# Audio_Codec.net
KiCad netlist of a schematic drawn in Altium Designer
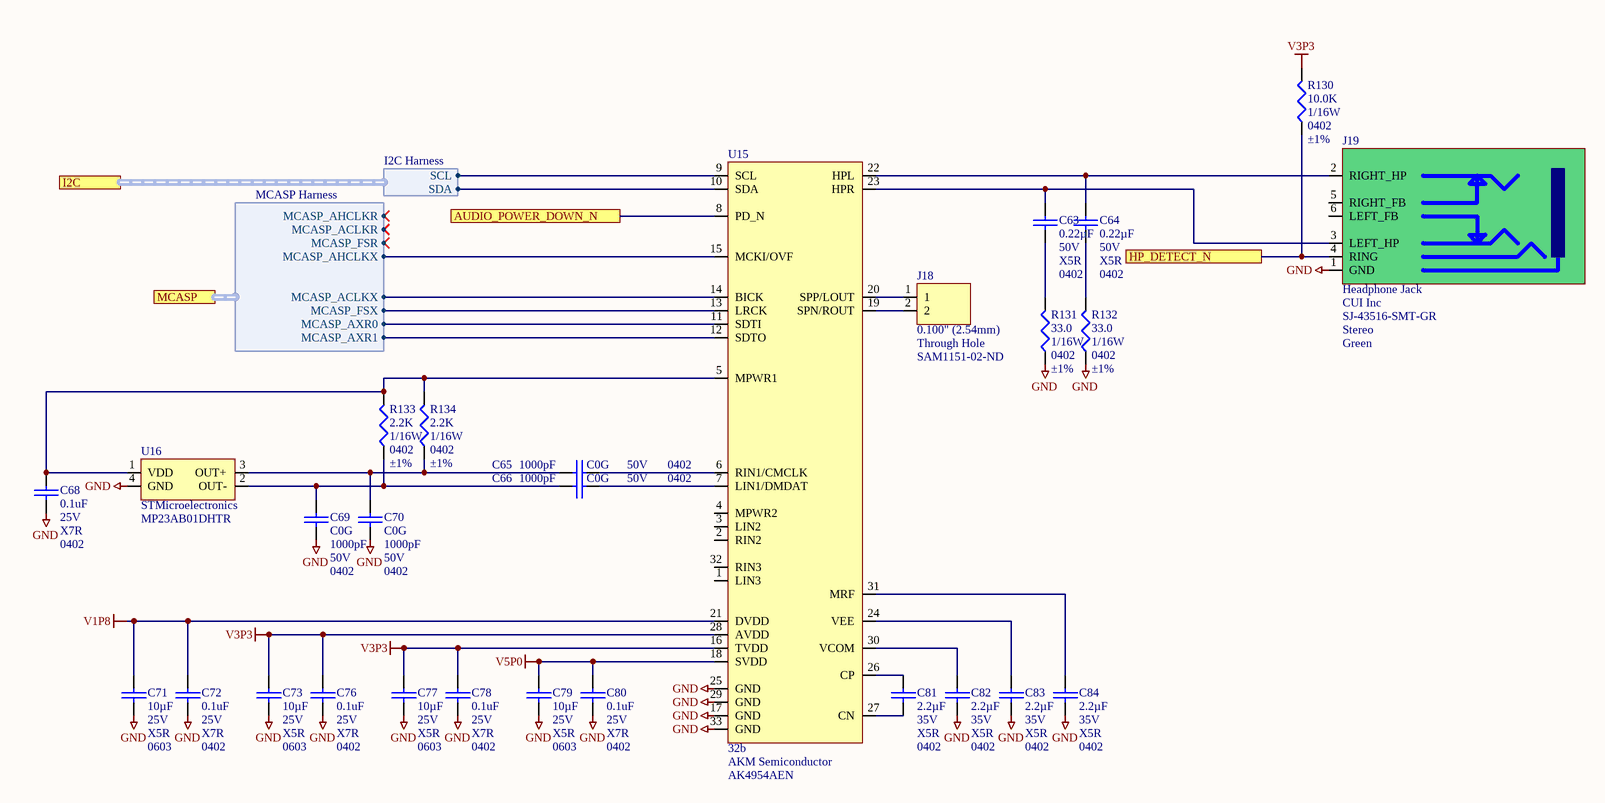
[diagram p0: Audio Codec.SchDoc]

(export (version "E")
  (design (tool "Eeschema 10.0.6"))
  (components
    (comp (ref "C63")
      (value "C_0402_0.22UF_50V")
      (footprint "C_ERA-0402")
      (description "CAP CER 0.22UF 50V X5R 0402")
      (fields
        (field (name "MANUFACTURER") "Taiyo Yuden")
        (field (name "MANUFACTURER PART NUMBER") "UMK105BJ224KV-F")
        (field (name "CAPACITANCE") "0.22µF")
        (field (name "VOLTAGE - RATED") "50V")
        (field (name "TEMPERATURE COEFFICIENT") "X5R")
        (field (name "PACKAGE / CASE") "0402")
      )
      (libsource (lib "Main Library") (part "C_0402_0.22UF_50V"))
    )
    (comp (ref "C64")
      (value "C_0402_0.22UF_50V")
      (footprint "C_ERA-0402")
      (description "CAP CER 0.22UF 50V X5R 0402")
      (fields
        (field (name "MANUFACTURER") "Taiyo Yuden")
        (field (name "MANUFACTURER PART NUMBER") "UMK105BJ224KV-F")
        (field (name "CAPACITANCE") "0.22µF")
        (field (name "VOLTAGE - RATED") "50V")
        (field (name "TEMPERATURE COEFFICIENT") "X5R")
        (field (name "PACKAGE / CASE") "0402")
      )
      (libsource (lib "Main Library") (part "C_0402_0.22UF_50V"))
    )
    (comp (ref "C65")
      (value "1000pF")
      (footprint "C_ERA-0402")
      (description "CAP CER 1000PF 50V C0G 0402")
      (fields
        (field (name "MANUFACTURER") "Murata Electronics North America")
        (field (name "MANUFACTURER PART NUMBER") "GRM1555C1H102JA01D")
        (field (name "TEMPERATURE COEFFICIENT") "C0G")
        (field (name "CAPACITANCE") "1000pF")
        (field (name "VOLTAGE - RATED") "50V")
        (field (name "PACKAGE / CASE") "0402")
      )
      (libsource (lib "Main Library") (part "C_0402_1000PF_50V"))
    )
    (comp (ref "C66")
      (value "1000pF")
      (footprint "C_ERA-0402")
      (description "CAP CER 1000PF 50V C0G 0402")
      (fields
        (field (name "MANUFACTURER") "Murata Electronics North America")
        (field (name "MANUFACTURER PART NUMBER") "GRM1555C1H102JA01D")
        (field (name "TEMPERATURE COEFFICIENT") "C0G")
        (field (name "CAPACITANCE") "1000pF")
        (field (name "VOLTAGE - RATED") "50V")
        (field (name "PACKAGE / CASE") "0402")
      )
      (libsource (lib "Main Library") (part "C_0402_1000PF_50V"))
    )
    (comp (ref "C68")
      (value "C_0402_0.1UF_25V")
      (footprint "C_0402")
      (description "CAP CER 0.1UF 25V X6S 0402")
      (fields
        (field (name "TOLERANCE") "10%")
        (field (name "CAPACITANCE") "0.1uF")
        (field (name "VOLTAGE - RATED") "25V")
        (field (name "TEMPERATURE COEFFICIENT") "X7R")
        (field (name "PACKAGE / CASE") "0402")
      )
      (libsource (lib "Cospan Design") (part "C_0402_0.1UF_25V"))
    )
    (comp (ref "C69")
      (value "1000pF")
      (footprint "C_ERA-0402")
      (description "CAP CER 1000PF 50V C0G 0402")
      (fields
        (field (name "MANUFACTURER") "Murata Electronics North America")
        (field (name "MANUFACTURER PART NUMBER") "GRM1555C1H102JA01D")
        (field (name "TEMPERATURE COEFFICIENT") "C0G")
        (field (name "CAPACITANCE") "1000pF")
        (field (name "VOLTAGE - RATED") "50V")
        (field (name "PACKAGE / CASE") "0402")
      )
      (libsource (lib "Main Library") (part "C_0402_1000PF_50V"))
    )
    (comp (ref "C70")
      (value "1000pF")
      (footprint "C_ERA-0402")
      (description "CAP CER 1000PF 50V C0G 0402")
      (fields
        (field (name "MANUFACTURER") "Murata Electronics North America")
        (field (name "MANUFACTURER PART NUMBER") "GRM1555C1H102JA01D")
        (field (name "TEMPERATURE COEFFICIENT") "C0G")
        (field (name "CAPACITANCE") "1000pF")
        (field (name "VOLTAGE - RATED") "50V")
        (field (name "PACKAGE / CASE") "0402")
      )
      (libsource (lib "Main Library") (part "C_0402_1000PF_50V"))
    )
    (comp (ref "C71")
      (value "C_0603_10µF")
      (footprint "C_ERA-0603")
      (description "CAP CER 10UF 16V X5R 0603")
      (fields
        (field (name "MANUFACTURER") "Murata Electronics North America")
        (field (name "MANUFACTURER PART NUMBER") "GRM188R61C106MA73D")
        (field (name "CAPACITANCE") "10µF")
        (field (name "VOLTAGE - RATED") "25V")
        (field (name "TEMPERATURE COEFFICIENT") "X5R")
        (field (name "PACKAGE / CASE") "0603")
      )
      (libsource (lib "Cospan Design") (part "C_0603_10µF"))
    )
    (comp (ref "C72")
      (value "C_0402_0.1UF_25V")
      (footprint "C_0402")
      (description "CAP CER 0.1UF 25V X6S 0402")
      (fields
        (field (name "TOLERANCE") "10%")
        (field (name "CAPACITANCE") "0.1uF")
        (field (name "VOLTAGE - RATED") "25V")
        (field (name "TEMPERATURE COEFFICIENT") "X7R")
        (field (name "PACKAGE / CASE") "0402")
      )
      (libsource (lib "Cospan Design") (part "C_0402_0.1UF_25V"))
    )
    (comp (ref "C73")
      (value "C_0603_10µF")
      (footprint "C_ERA-0603")
      (description "CAP CER 10UF 16V X5R 0603")
      (fields
        (field (name "MANUFACTURER") "Murata Electronics North America")
        (field (name "MANUFACTURER PART NUMBER") "GRM188R61C106MA73D")
        (field (name "CAPACITANCE") "10µF")
        (field (name "VOLTAGE - RATED") "25V")
        (field (name "TEMPERATURE COEFFICIENT") "X5R")
        (field (name "PACKAGE / CASE") "0603")
      )
      (libsource (lib "Cospan Design") (part "C_0603_10µF"))
    )
    (comp (ref "C76")
      (value "C_0402_0.1UF_25V")
      (footprint "C_0402")
      (description "CAP CER 0.1UF 25V X6S 0402")
      (fields
        (field (name "TOLERANCE") "10%")
        (field (name "CAPACITANCE") "0.1uF")
        (field (name "VOLTAGE - RATED") "25V")
        (field (name "TEMPERATURE COEFFICIENT") "X7R")
        (field (name "PACKAGE / CASE") "0402")
      )
      (libsource (lib "Cospan Design") (part "C_0402_0.1UF_25V"))
    )
    (comp (ref "C77")
      (value "C_0603_10µF")
      (footprint "C_ERA-0603")
      (description "CAP CER 10UF 16V X5R 0603")
      (fields
        (field (name "MANUFACTURER") "Murata Electronics North America")
        (field (name "MANUFACTURER PART NUMBER") "GRM188R61C106MA73D")
        (field (name "CAPACITANCE") "10µF")
        (field (name "VOLTAGE - RATED") "25V")
        (field (name "TEMPERATURE COEFFICIENT") "X5R")
        (field (name "PACKAGE / CASE") "0603")
      )
      (libsource (lib "Cospan Design") (part "C_0603_10µF"))
    )
    (comp (ref "C78")
      (value "C_0402_0.1UF_25V")
      (footprint "C_0402")
      (description "CAP CER 0.1UF 25V X6S 0402")
      (fields
        (field (name "TOLERANCE") "10%")
        (field (name "CAPACITANCE") "0.1uF")
        (field (name "VOLTAGE - RATED") "25V")
        (field (name "TEMPERATURE COEFFICIENT") "X7R")
        (field (name "PACKAGE / CASE") "0402")
      )
      (libsource (lib "Cospan Design") (part "C_0402_0.1UF_25V"))
    )
    (comp (ref "C79")
      (value "C_0603_10µF")
      (footprint "C_ERA-0603")
      (description "CAP CER 10UF 16V X5R 0603")
      (fields
        (field (name "MANUFACTURER") "Murata Electronics North America")
        (field (name "MANUFACTURER PART NUMBER") "GRM188R61C106MA73D")
        (field (name "CAPACITANCE") "10µF")
        (field (name "VOLTAGE - RATED") "25V")
        (field (name "TEMPERATURE COEFFICIENT") "X5R")
        (field (name "PACKAGE / CASE") "0603")
      )
      (libsource (lib "Cospan Design") (part "C_0603_10µF"))
    )
    (comp (ref "C80")
      (value "C_0402_0.1UF_25V")
      (footprint "C_0402")
      (description "CAP CER 0.1UF 25V X6S 0402")
      (fields
        (field (name "TOLERANCE") "10%")
        (field (name "CAPACITANCE") "0.1uF")
        (field (name "VOLTAGE - RATED") "25V")
        (field (name "TEMPERATURE COEFFICIENT") "X7R")
        (field (name "PACKAGE / CASE") "0402")
      )
      (libsource (lib "Cospan Design") (part "C_0402_0.1UF_25V"))
    )
    (comp (ref "C81")
      (value "C_0402_2.2uF_35V")
      (footprint "C_ERA-0402")
      (description "CAP CER 2.2UF 35V 20% X5R 0402")
      (fields
        (field (name "MANUFACTURER") "TDK Corporation")
        (field (name "MANUFACTURER PART NUMBER") "C1005X5R1V225K050BC")
        (field (name "CAPACITANCE") "2.2µF")
        (field (name "VOLTAGE - RATED") "35V")
        (field (name "TEMPERATURE COEFFICIENT") "X5R")
        (field (name "PACKAGE / CASE") "0402")
      )
      (libsource (lib "Main Library") (part "C_0402_2.2uF_35V"))
    )
    (comp (ref "C82")
      (value "C_0402_2.2uF_35V")
      (footprint "C_ERA-0402")
      (description "CAP CER 2.2UF 35V 20% X5R 0402")
      (fields
        (field (name "MANUFACTURER") "TDK Corporation")
        (field (name "MANUFACTURER PART NUMBER") "C1005X5R1V225K050BC")
        (field (name "CAPACITANCE") "2.2µF")
        (field (name "VOLTAGE - RATED") "35V")
        (field (name "TEMPERATURE COEFFICIENT") "X5R")
        (field (name "PACKAGE / CASE") "0402")
      )
      (libsource (lib "Main Library") (part "C_0402_2.2uF_35V"))
    )
    (comp (ref "C83")
      (value "C_0402_2.2uF_35V")
      (footprint "C_ERA-0402")
      (description "CAP CER 2.2UF 35V 20% X5R 0402")
      (fields
        (field (name "MANUFACTURER") "TDK Corporation")
        (field (name "MANUFACTURER PART NUMBER") "C1005X5R1V225K050BC")
        (field (name "CAPACITANCE") "2.2µF")
        (field (name "VOLTAGE - RATED") "35V")
        (field (name "TEMPERATURE COEFFICIENT") "X5R")
        (field (name "PACKAGE / CASE") "0402")
      )
      (libsource (lib "Main Library") (part "C_0402_2.2uF_35V"))
    )
    (comp (ref "C84")
      (value "C_0402_2.2uF_35V")
      (footprint "C_ERA-0402")
      (description "CAP CER 2.2UF 35V 20% X5R 0402")
      (fields
        (field (name "MANUFACTURER") "TDK Corporation")
        (field (name "MANUFACTURER PART NUMBER") "C1005X5R1V225K050BC")
        (field (name "CAPACITANCE") "2.2µF")
        (field (name "VOLTAGE - RATED") "35V")
        (field (name "TEMPERATURE COEFFICIENT") "X5R")
        (field (name "PACKAGE / CASE") "0402")
      )
      (libsource (lib "Main Library") (part "C_0402_2.2uF_35V"))
    )
    (comp (ref "J18")
      (value "J_HDR1X2_THRHOLE_VERT_FEMALE")
      (footprint "1X2_HOLES_VERTICAL_FEMALE_HEADRER")
      (description "CONN RCPT .100\" 2POS SNGL HORZ")
      (fields
        (field (name "MANUFACTURER") "Samtec Inc")
        (field (name "MANUFACTURER PART NUMBER") "SSM-102-S-SH")
        (field (name "PITCH") "0.100\" (2.54mm)")
        (field (name "MOUNTING TYPE") "Through Hole")
        (field (name "SUPPLIER PART NUMBER 1") "SAM1151-02-ND")
      )
      (libsource (lib "Main Library") (part "J_HDR1X2_THRHOLE_VERT_FEMALE"))
    )
    (comp (ref "J19")
      (value "Headphone Jack")
      (footprint "HEADPHONE_JACK")
      (description "CONN AUDIO JACK 3.5MM 4COND SMD")
      (fields
        (field (name "MANUFACTURER") "CUI Inc")
        (field (name "MANUFACTURER PART NUMBER") "SJ-43516-SMT-GR")
        (field (name "SIGNAL LINES") "Stereo")
        (field (name "COLOR") "Green")
      )
      (libsource (lib "Main Library") (part "J_HEADPHONE_JACK"))
    )
    (comp (ref "R130")
      (value "R_0402_10.0K")
      (footprint "R_0402")
      (description "RES 10.0K OHM 1/16W 1% 0402 SMD")
      (fields
        (field (name "MANUFACTURER") "Stackpole Electronics Inc")
        (field (name "MANUFACTURER PART NUMBER") "RMCF0402FT10K0")
        (field (name "RESISTANCE IN OHMS") "10.0K")
        (field (name "POWER (WATTS)") "1/16W")
        (field (name "CASE") "0402")
        (field (name "TOLERANCE") "±1%")
      )
      (libsource (lib "Main Library") (part "R_0402_10.0K"))
    )
    (comp (ref "R131")
      (value "R_0402_33")
      (footprint "R_0402")
      (description "RES 33.0 OHM 1/16W 1% 0402 SMD")
      (fields
        (field (name "MANUFACTURER") "Yageo")
        (field (name "MANUFACTURER PART NUMBER") "RC0402FR-0733RL")
        (field (name "RESISTANCE IN OHMS") "33.0")
        (field (name "POWER (WATTS)") "1/16W")
        (field (name "CASE") "0402")
        (field (name "TOLERANCE") "±1%")
      )
      (libsource (lib "Main Library") (part "R_0402_33"))
    )
    (comp (ref "R132")
      (value "R_0402_33")
      (footprint "R_0402")
      (description "RES 33.0 OHM 1/16W 1% 0402 SMD")
      (fields
        (field (name "MANUFACTURER") "Yageo")
        (field (name "MANUFACTURER PART NUMBER") "RC0402FR-0733RL")
        (field (name "RESISTANCE IN OHMS") "33.0")
        (field (name "POWER (WATTS)") "1/16W")
        (field (name "CASE") "0402")
        (field (name "TOLERANCE") "±1%")
      )
      (libsource (lib "Main Library") (part "R_0402_33"))
    )
    (comp (ref "R133")
      (value "R_0402_2.2K")
      (footprint "R_0402")
      (description "RES SMD 2.2K OHM 1% 1/10W 0402")
      (fields
        (field (name "MANUFACTURER") "Panasonic Electronic Components")
        (field (name "MANUFACTURER PART NUMBER") "ERJ-2RKF2201X")
        (field (name "RESISTANCE IN OHMS") "2.2K")
        (field (name "POWER (WATTS)") "1/16W")
        (field (name "CASE") "0402")
        (field (name "TOLERANCE") "±1%")
      )
      (libsource (lib "Cospan Design") (part "R_0402_2.2K"))
    )
    (comp (ref "R134")
      (value "R_0402_2.2K")
      (footprint "R_0402")
      (description "RES SMD 2.2K OHM 1% 1/10W 0402")
      (fields
        (field (name "MANUFACTURER") "Panasonic Electronic Components")
        (field (name "MANUFACTURER PART NUMBER") "ERJ-2RKF2201X")
        (field (name "RESISTANCE IN OHMS") "2.2K")
        (field (name "POWER (WATTS)") "1/16W")
        (field (name "CASE") "0402")
        (field (name "TOLERANCE") "±1%")
      )
      (libsource (lib "Cospan Design") (part "R_0402_2.2K"))
    )
    (comp (ref "U15")
      (value "U_AK4954AEN")
      (footprint "QFN40P400X400X80_HS-33N")
      (description "IC STEREO CODEC 32BIT 32QFN")
      (fields
        (field (name "RESOLUTION") "32b")
        (field (name "MANUFACTURER 1") "AKM Semiconductor")
        (field (name "MANUFACTURER PART NUMBER 1") "AK4954AEN")
      )
      (libsource (lib "Cospan Design") (part "U_AK4954AEN"))
    )
    (comp (ref "U16")
      (value "U_MP23AB01DHTR")
      (footprint "RHLGA")
      (description "MIC MEMS ANALOG OMNI -38DB")
      (fields
        (field (name "MANUFACTURER 1") "STMicroelectronics")
        (field (name "MANUFACTURER PART NUMBER 1") "MP23AB01DHTR")
      )
      (libsource (lib "Cospan Design") (part "U_MP23AB01DHTR"))
    )
  )
  (nets
    (net (code "4") (name "/AUDIO_POWER_DOWN_N") (class "Default")
      (node (ref "U15") (pin "8") (pinfunction "PD_N_8") (pintype "passive"))
    )
    (net (code "5") (name "/HP_DETECT_N") (class "Default")
      (node (ref "J19") (pin "4") (pinfunction "RING_4") (pintype "passive"))
      (node (ref "R130") (pin "2") (pinfunction "2_2") (pintype "passive"))
    )
    (net (code "6") (name "/MCASP_ACLKX") (class "Default")
      (node (ref "U15") (pin "14") (pinfunction "BICK_14") (pintype "passive"))
    )
    (net (code "7") (name "/MCASP_AHCLKX") (class "Default")
      (node (ref "U15") (pin "15") (pinfunction "MCKI/OVF_15") (pintype "passive"))
    )
    (net (code "8") (name "/MCASP_AXR0") (class "Default")
      (node (ref "U15") (pin "11") (pinfunction "SDTI_11") (pintype "passive"))
    )
    (net (code "9") (name "/MCASP_AXR1") (class "Default")
      (node (ref "U15") (pin "12") (pinfunction "SDTO_12") (pintype "passive"))
    )
    (net (code "10") (name "/MCASP_FSX") (class "Default")
      (node (ref "U15") (pin "13") (pinfunction "LRCK_13") (pintype "passive"))
    )
    (net (code "11") (name "/SCL") (class "Default")
      (node (ref "U15") (pin "9") (pinfunction "SCL_9") (pintype "passive"))
    )
    (net (code "12") (name "/SDA") (class "Default")
      (node (ref "U15") (pin "10") (pinfunction "SDA_10") (pintype "passive"))
    )
    (net (code "15") (name "GND") (class "Default")
      (node (ref "C68") (pin "1") (pinfunction "1_1") (pintype "passive"))
      (node (ref "C69") (pin "2") (pinfunction "2_2") (pintype "passive"))
      (node (ref "C70") (pin "2") (pinfunction "2_2") (pintype "passive"))
      (node (ref "C71") (pin "1") (pinfunction "1_1") (pintype "passive"))
      (node (ref "C72") (pin "1") (pinfunction "1_1") (pintype "passive"))
      (node (ref "C73") (pin "1") (pinfunction "1_1") (pintype "passive"))
      (node (ref "C76") (pin "1") (pinfunction "1_1") (pintype "passive"))
      (node (ref "C77") (pin "1") (pinfunction "1_1") (pintype "passive"))
      (node (ref "C78") (pin "1") (pinfunction "1_1") (pintype "passive"))
      (node (ref "C79") (pin "1") (pinfunction "1_1") (pintype "passive"))
      (node (ref "C80") (pin "1") (pinfunction "1_1") (pintype "passive"))
      (node (ref "C82") (pin "1") (pinfunction "1_1") (pintype "passive"))
      (node (ref "C83") (pin "1") (pinfunction "1_1") (pintype "passive"))
      (node (ref "C84") (pin "1") (pinfunction "1_1") (pintype "passive"))
      (node (ref "J19") (pin "1") (pinfunction "GND_1") (pintype "passive"))
      (node (ref "R131") (pin "2") (pinfunction "2_2") (pintype "passive"))
      (node (ref "R132") (pin "2") (pinfunction "2_2") (pintype "passive"))
      (node (ref "U15") (pin "17") (pinfunction "GND_17") (pintype "passive"))
      (node (ref "U15") (pin "25") (pinfunction "GND_25") (pintype "passive"))
      (node (ref "U15") (pin "29") (pinfunction "GND_29") (pintype "passive"))
      (node (ref "U15") (pin "33") (pinfunction "GND_33") (pintype "passive"))
      (node (ref "U16") (pin "4") (pinfunction "GND_4") (pintype "passive"))
    )
    (net (code "16") (name "Net-(C63-Pad1)") (class "Default")
      (node (ref "C63") (pin "1") (pinfunction "1_1") (pintype "passive"))
      (node (ref "R131") (pin "1") (pinfunction "1_1") (pintype "passive"))
    )
    (net (code "17") (name "Net-(C64-Pad1)") (class "Default")
      (node (ref "C64") (pin "1") (pinfunction "1_1") (pintype "passive"))
      (node (ref "R132") (pin "1") (pinfunction "1_1") (pintype "passive"))
    )
    (net (code "18") (name "Net-(J19-LEFT_HP)") (class "Default")
      (node (ref "C63") (pin "2") (pinfunction "2_2") (pintype "passive"))
      (node (ref "J19") (pin "3") (pinfunction "LEFT_HP_3") (pintype "passive"))
      (node (ref "U15") (pin "23") (pinfunction "HPR_23") (pintype "passive"))
    )
    (net (code "19") (name "Net-(J19-RIGHT_HP)") (class "Default")
      (node (ref "C64") (pin "2") (pinfunction "2_2") (pintype "passive"))
      (node (ref "J19") (pin "2") (pinfunction "RIGHT_HP_2") (pintype "passive"))
      (node (ref "U15") (pin "22") (pinfunction "HPL_22") (pintype "passive"))
    )
    (net (code "20") (name "Net-(U15-CN)") (class "Default")
      (node (ref "C81") (pin "1") (pinfunction "1_1") (pintype "passive"))
      (node (ref "U15") (pin "27") (pinfunction "CN_27") (pintype "passive"))
    )
    (net (code "21") (name "Net-(U15-CP)") (class "Default")
      (node (ref "C81") (pin "2") (pinfunction "2_2") (pintype "passive"))
      (node (ref "U15") (pin "26") (pinfunction "CP_26") (pintype "passive"))
    )
    (net (code "22") (name "Net-(U15-LIN1{slash}DMDAT)") (class "Default")
      (node (ref "C66") (pin "1") (pinfunction "1_1") (pintype "passive"))
      (node (ref "U15") (pin "7") (pinfunction "LIN1/DMDAT_7") (pintype "passive"))
    )
    (net (code "23") (name "Net-(U15-MPWR1)") (class "Default")
      (node (ref "C68") (pin "2") (pinfunction "2_2") (pintype "passive"))
      (node (ref "R133") (pin "1") (pinfunction "1_1") (pintype "passive"))
      (node (ref "R134") (pin "1") (pinfunction "1_1") (pintype "passive"))
      (node (ref "U15") (pin "5") (pinfunction "MPWR1_5") (pintype "passive"))
      (node (ref "U16") (pin "1") (pinfunction "VDD_1") (pintype "passive"))
    )
    (net (code "24") (name "Net-(U15-MRF)") (class "Default")
      (node (ref "C84") (pin "2") (pinfunction "2_2") (pintype "passive"))
      (node (ref "U15") (pin "31") (pinfunction "MRF_31") (pintype "passive"))
    )
    (net (code "25") (name "Net-(U15-RIN1{slash}CMCLK)") (class "Default")
      (node (ref "C65") (pin "1") (pinfunction "1_1") (pintype "passive"))
      (node (ref "U15") (pin "6") (pinfunction "RIN1/CMCLK_6") (pintype "passive"))
    )
    (net (code "26") (name "Net-(U15-SPN{slash}ROUT)") (class "Default")
      (node (ref "J18") (pin "2") (pinfunction "2_2") (pintype "passive"))
      (node (ref "U15") (pin "19") (pinfunction "SPN/ROUT_19") (pintype "passive"))
    )
    (net (code "27") (name "Net-(U15-SPP{slash}LOUT)") (class "Default")
      (node (ref "J18") (pin "1") (pinfunction "1_1") (pintype "passive"))
      (node (ref "U15") (pin "20") (pinfunction "SPP/LOUT_20") (pintype "passive"))
    )
    (net (code "28") (name "Net-(U15-VCOM)") (class "Default")
      (node (ref "C82") (pin "2") (pinfunction "2_2") (pintype "passive"))
      (node (ref "U15") (pin "30") (pinfunction "VCOM_30") (pintype "passive"))
    )
    (net (code "29") (name "Net-(U15-VEE)") (class "Default")
      (node (ref "C83") (pin "2") (pinfunction "2_2") (pintype "passive"))
      (node (ref "U15") (pin "24") (pinfunction "VEE_24") (pintype "passive"))
    )
    (net (code "30") (name "Net-(U16-OUT+)") (class "Default")
      (node (ref "C65") (pin "2") (pinfunction "2_2") (pintype "passive"))
      (node (ref "C70") (pin "1") (pinfunction "1_1") (pintype "passive"))
      (node (ref "R134") (pin "2") (pinfunction "2_2") (pintype "passive"))
      (node (ref "U16") (pin "3") (pinfunction "OUT+_3") (pintype "passive"))
    )
    (net (code "31") (name "Net-(U16-OUT-)") (class "Default")
      (node (ref "C66") (pin "2") (pinfunction "2_2") (pintype "passive"))
      (node (ref "C69") (pin "1") (pinfunction "1_1") (pintype "passive"))
      (node (ref "R133") (pin "2") (pinfunction "2_2") (pintype "passive"))
      (node (ref "U16") (pin "2") (pinfunction "OUT-_2") (pintype "passive"))
    )
    (net (code "32") (name "V1P8") (class "Default")
      (node (ref "C71") (pin "2") (pinfunction "2_2") (pintype "passive"))
      (node (ref "C72") (pin "2") (pinfunction "2_2") (pintype "passive"))
      (node (ref "U15") (pin "21") (pinfunction "DVDD_21") (pintype "passive"))
    )
    (net (code "33") (name "V3P3") (class "Default")
      (node (ref "C73") (pin "2") (pinfunction "2_2") (pintype "passive"))
      (node (ref "C76") (pin "2") (pinfunction "2_2") (pintype "passive"))
      (node (ref "C77") (pin "2") (pinfunction "2_2") (pintype "passive"))
      (node (ref "C78") (pin "2") (pinfunction "2_2") (pintype "passive"))
      (node (ref "R130") (pin "1") (pinfunction "1_1") (pintype "passive"))
      (node (ref "U15") (pin "16") (pinfunction "TVDD_16") (pintype "passive"))
      (node (ref "U15") (pin "28") (pinfunction "AVDD_28") (pintype "passive"))
    )
    (net (code "34") (name "V5P0") (class "Default")
      (node (ref "C79") (pin "2") (pinfunction "2_2") (pintype "passive"))
      (node (ref "C80") (pin "2") (pinfunction "2_2") (pintype "passive"))
      (node (ref "U15") (pin "18") (pinfunction "SVDD_18") (pintype "passive"))
    )
    (net (code "35") (name "unconnected-(J19-LEFT_FB-Pad6)") (class "Default")
      (node (ref "J19") (pin "6") (pinfunction "LEFT_FB_6") (pintype "passive"))
    )
    (net (code "36") (name "unconnected-(J19-RIGHT_FB-Pad5)") (class "Default")
      (node (ref "J19") (pin "5") (pinfunction "RIGHT_FB_5") (pintype "passive"))
    )
    (net (code "37") (name "unconnected-(U15-LIN2-Pad3)") (class "Default")
      (node (ref "U15") (pin "3") (pinfunction "LIN2_3") (pintype "passive"))
    )
    (net (code "38") (name "unconnected-(U15-LIN3-Pad1)") (class "Default")
      (node (ref "U15") (pin "1") (pinfunction "LIN3_1") (pintype "passive"))
    )
    (net (code "39") (name "unconnected-(U15-MPWR2-Pad4)") (class "Default")
      (node (ref "U15") (pin "4") (pinfunction "MPWR2_4") (pintype "passive"))
    )
    (net (code "40") (name "unconnected-(U15-RIN2-Pad2)") (class "Default")
      (node (ref "U15") (pin "2") (pinfunction "RIN2_2") (pintype "passive"))
    )
    (net (code "41") (name "unconnected-(U15-RIN3-Pad32)") (class "Default")
      (node (ref "U15") (pin "32") (pinfunction "RIN3_32") (pintype "passive"))
    )
  )
)
